# DVT-Buffer.net
KiCad netlist of a schematic drawn in Altium Designer
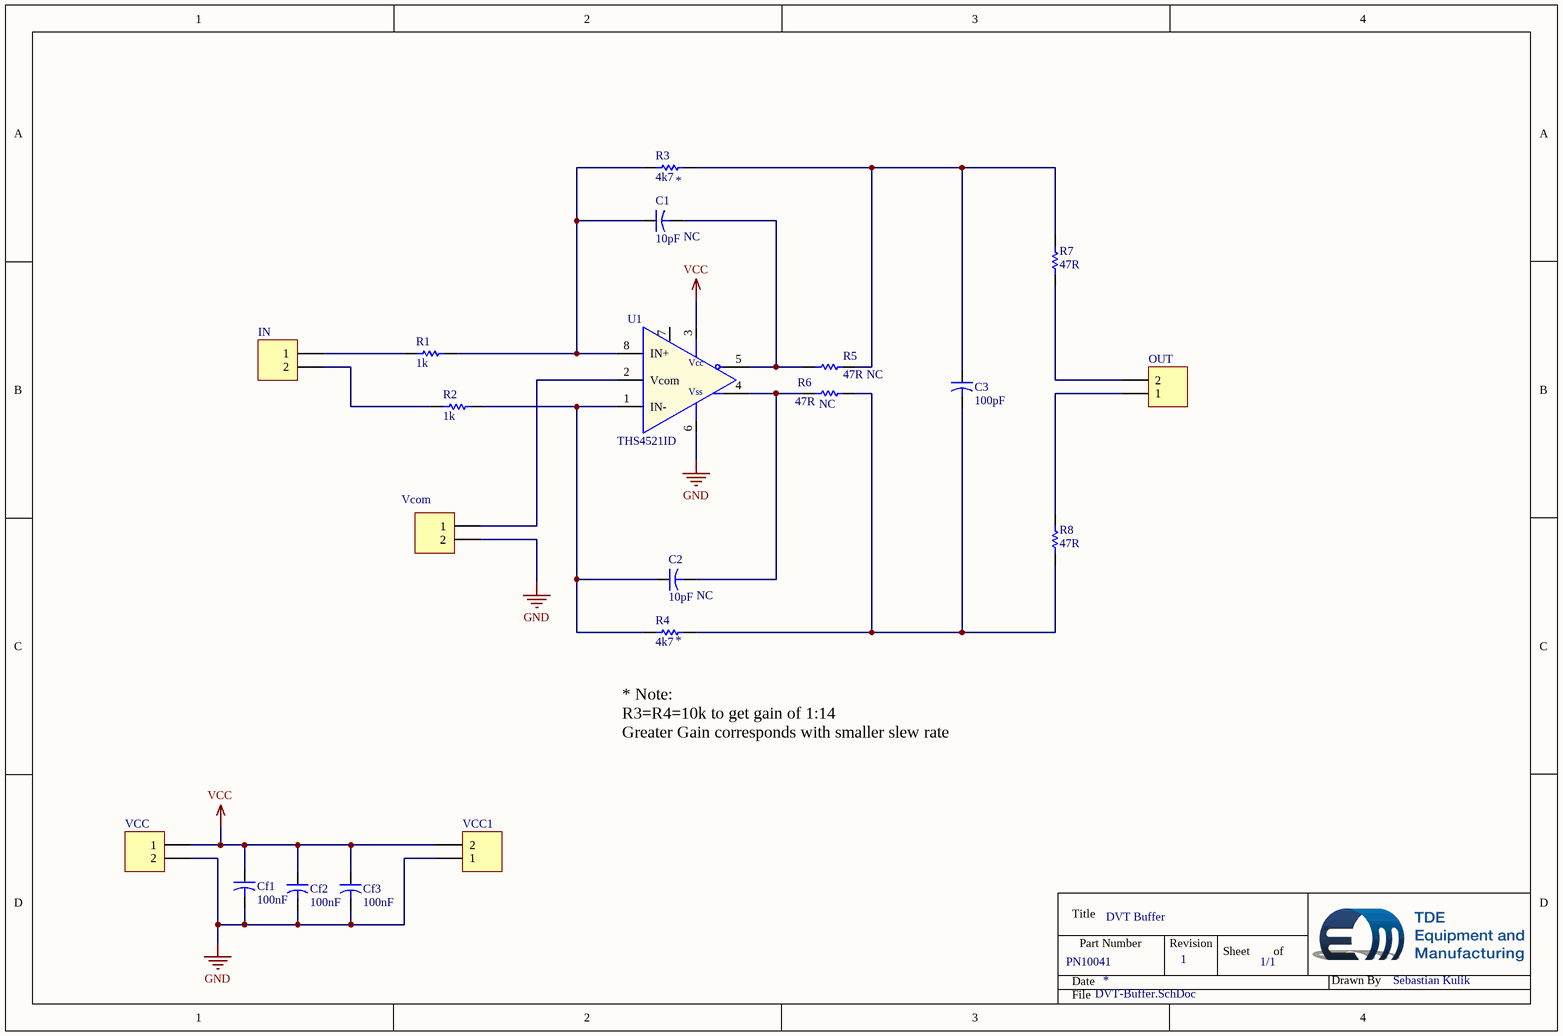
[diagram p0: DVT-Buffer.SchDoc]

(export (version "E")
  (design (tool "Eeschema 10.0.6"))
  (components
    (comp (ref "C1")
      (value "10pF")
      (footprint "Dummy-10mm")
      (description "Capacitor-Dummy-THT")
      (fields (field (name "PUBLISHER") "Sebastian Kulik"))
      (libsource (lib "Capacitors") (part "Capacitor-Dummy-THT"))
    )
    (comp (ref "C2")
      (value "10pF")
      (footprint "Dummy-10mm")
      (description "Capacitor-Dummy-THT")
      (fields (field (name "PUBLISHER") "Sebastian Kulik"))
      (libsource (lib "Capacitors") (part "Capacitor-Dummy-THT"))
    )
    (comp (ref "C3")
      (value "100pF")
      (footprint "Dummy-10mm")
      (description "Capacitor-Dummy-THT")
      (fields (field (name "PUBLISHER") "Sebastian Kulik"))
      (libsource (lib "Capacitors") (part "Capacitor-Dummy-THT"))
    )
    (comp (ref "Cf1")
      (value "100nF")
      (footprint "Dummy-10mm")
      (description "Capacitor-Dummy-THT")
      (fields (field (name "PUBLISHER") "Sebastian Kulik"))
      (libsource (lib "Capacitors") (part "Capacitor-Dummy-THT"))
    )
    (comp (ref "Cf2")
      (value "100nF")
      (footprint "Dummy-10mm")
      (description "Capacitor-Dummy-THT")
      (fields (field (name "PUBLISHER") "Sebastian Kulik"))
      (libsource (lib "Capacitors") (part "Capacitor-Dummy-THT"))
    )
    (comp (ref "Cf3")
      (value "100nF")
      (footprint "Dummy-10mm")
      (description "Capacitor-Dummy-THT")
      (fields (field (name "PUBLISHER") "Sebastian Kulik"))
      (libsource (lib "Capacitors") (part "Capacitor-Dummy-THT"))
    )
    (comp (ref "IN")
      (value "PHOENIX_1715721")
      (footprint "Phoenix-2-5_08")
      (description "Phoenix, 2 pol, 5.08mm, 22A, 715721")
      (fields (field (name "MANUFACTURER") "Phoenix") (field (name "PUBLISHER") "Sebastian Kulik"))
      (libsource (lib "") (part "2Pol_1715721_1"))
    )
    (comp (ref "OUT")
      (value "PHOENIX_1715721")
      (footprint "Phoenix-2-5_08")
      (description "Phoenix, 2 pol, 5.08mm, 22A, 715721")
      (fields (field (name "MANUFACTURER") "Phoenix") (field (name "PUBLISHER") "Sebastian Kulik"))
      (libsource (lib "Connectors") (part "2Pol_1715721"))
    )
    (comp (ref "R1")
      (value "1k")
      (footprint "Dummy-10mm")
      (description "Resistor-Dummy-THT")
      (fields (field (name "PUBLISHER") "Sebastian Kulik"))
      (libsource (lib "Resistors") (part "Resistor-Dummy-THT"))
    )
    (comp (ref "R2")
      (value "1k")
      (footprint "Dummy-10mm")
      (description "Resistor-Dummy-THT")
      (fields (field (name "PUBLISHER") "Sebastian Kulik"))
      (libsource (lib "Resistors") (part "Resistor-Dummy-THT"))
    )
    (comp (ref "R3")
      (value "4k7")
      (footprint "Dummy-10mm")
      (description "Resistor-Dummy-THT")
      (fields (field (name "PUBLISHER") "Sebastian Kulik"))
      (libsource (lib "Resistors") (part "Resistor-Dummy-THT"))
    )
    (comp (ref "R4")
      (value "4k7")
      (footprint "Dummy-10mm")
      (description "Resistor-Dummy-THT")
      (fields (field (name "PUBLISHER") "Sebastian Kulik"))
      (libsource (lib "Resistors") (part "Resistor-Dummy-THT"))
    )
    (comp (ref "R5")
      (value "47R")
      (footprint "Dummy-10mm")
      (description "Resistor-Dummy-THT")
      (fields (field (name "PUBLISHER") "Sebastian Kulik"))
      (libsource (lib "Resistors") (part "Resistor-Dummy-THT"))
    )
    (comp (ref "R6")
      (value "47R")
      (footprint "Dummy-10mm")
      (description "Resistor-Dummy-THT")
      (fields (field (name "PUBLISHER") "Sebastian Kulik"))
      (libsource (lib "Resistors") (part "Resistor-Dummy-THT"))
    )
    (comp (ref "R7")
      (value "47R")
      (footprint "Dummy-10mm")
      (description "Resistor-Dummy-THT")
      (fields (field (name "PUBLISHER") "Sebastian Kulik"))
      (libsource (lib "Resistors") (part "Resistor-Dummy-THT"))
    )
    (comp (ref "R8")
      (value "47R")
      (footprint "Dummy-10mm")
      (description "Resistor-Dummy-THT")
      (fields (field (name "PUBLISHER") "Sebastian Kulik"))
      (libsource (lib "Resistors") (part "Resistor-Dummy-THT"))
    )
    (comp (ref "U1")
      (value "THS4521ID")
      (footprint "TSSOP8")
      (description "Fully differential OP, 50MHz")
      (fields (field (name "MANUFACTURER") "TI") (field (name "PUBLISHER") "Sebastian Kulik"))
      (libsource (lib "ICs") (part "THS4521ID"))
    )
    (comp (ref "VCC")
      (value "PHOENIX_1715721")
      (footprint "Phoenix-2-5_08")
      (description "Phoenix, 2 pol, 5.08mm, 22A, 715721")
      (fields (field (name "MANUFACTURER") "Phoenix") (field (name "PUBLISHER") "Sebastian Kulik"))
      (libsource (lib "") (part "2Pol_1715721_1"))
    )
    (comp (ref "VCC1")
      (value "PHOENIX_1715721")
      (footprint "Phoenix-2-5_08")
      (description "Phoenix, 2 pol, 5.08mm, 22A, 715721")
      (fields (field (name "MANUFACTURER") "Phoenix") (field (name "PUBLISHER") "Sebastian Kulik"))
      (libsource (lib "Connectors") (part "2Pol_1715721"))
    )
    (comp (ref "Vcom")
      (value "Plug_2_90_2.54")
      (footprint "HDR1X2")
      (description "Plug, 2-Pin")
      (fields (field (name "MANUFACTURER") "WE") (field (name "PUBLISHER") "Sebastian Kulik"))
      (libsource (lib "Connectors") (part "Plug_2_90_2.54"))
    )
  )
  (nets
    (net (code "1") (name "GND") (class "Default")
      (node (ref "Cf1") (pin "2") (pinfunction "2_2") (pintype "passive"))
      (node (ref "Cf2") (pin "2") (pinfunction "2_2") (pintype "passive"))
      (node (ref "Cf3") (pin "2") (pinfunction "2_2") (pintype "passive"))
      (node (ref "U1") (pin "6") (pinfunction "Vss_6") (pintype "passive"))
      (node (ref "VCC") (pin "2") (pinfunction "2_2") (pintype "passive"))
      (node (ref "VCC1") (pin "1") (pinfunction "1_1") (pintype "passive"))
      (node (ref "Vcom") (pin "2") (pinfunction "2_2") (pintype "passive"))
    )
    (net (code "2") (name "Net-(C3-Pad1)") (class "Default")
      (node (ref "C3") (pin "1") (pinfunction "1_1") (pintype "passive"))
      (node (ref "R3") (pin "2") (pinfunction "2_2") (pintype "passive"))
      (node (ref "R5") (pin "2") (pinfunction "2_2") (pintype "passive"))
      (node (ref "R7") (pin "2") (pinfunction "2_2") (pintype "passive"))
    )
    (net (code "3") (name "Net-(C3-Pad2)") (class "Default")
      (node (ref "C3") (pin "2") (pinfunction "2_2") (pintype "passive"))
      (node (ref "R4") (pin "2") (pinfunction "2_2") (pintype "passive"))
      (node (ref "R6") (pin "2") (pinfunction "2_2") (pintype "passive"))
      (node (ref "R8") (pin "1") (pinfunction "1_1") (pintype "passive"))
    )
    (net (code "4") (name "Net-(IN-Pad1)") (class "Default")
      (node (ref "IN") (pin "1") (pinfunction "1_1") (pintype "passive"))
      (node (ref "R1") (pin "1") (pinfunction "1_1") (pintype "passive"))
    )
    (net (code "5") (name "Net-(IN-Pad2)") (class "Default")
      (node (ref "IN") (pin "2") (pinfunction "2_2") (pintype "passive"))
      (node (ref "R2") (pin "1") (pinfunction "1_1") (pintype "passive"))
    )
    (net (code "6") (name "Net-(OUT-Pad1)") (class "Default")
      (node (ref "OUT") (pin "1") (pinfunction "1_1") (pintype "passive"))
      (node (ref "R8") (pin "2") (pinfunction "2_2") (pintype "passive"))
    )
    (net (code "7") (name "Net-(OUT-Pad2)") (class "Default")
      (node (ref "OUT") (pin "2") (pinfunction "2_2") (pintype "passive"))
      (node (ref "R7") (pin "1") (pinfunction "1_1") (pintype "passive"))
    )
    (net (code "8") (name "Net-(U1-IN+)") (class "Default")
      (node (ref "C1") (pin "1") (pinfunction "1_1") (pintype "passive"))
      (node (ref "R1") (pin "2") (pinfunction "2_2") (pintype "passive"))
      (node (ref "R3") (pin "1") (pinfunction "1_1") (pintype "passive"))
      (node (ref "U1") (pin "8") (pinfunction "IN+_8") (pintype "power_in"))
    )
    (net (code "9") (name "Net-(U1-IN-)") (class "Default")
      (node (ref "C2") (pin "1") (pinfunction "1_1") (pintype "passive"))
      (node (ref "R2") (pin "2") (pinfunction "2_2") (pintype "passive"))
      (node (ref "R4") (pin "1") (pinfunction "1_1") (pintype "passive"))
      (node (ref "U1") (pin "1") (pinfunction "IN-_1") (pintype "passive"))
    )
    (net (code "10") (name "Net-(U1-OUT+)") (class "Default")
      (node (ref "C1") (pin "2") (pinfunction "2_2") (pintype "passive"))
      (node (ref "R5") (pin "1") (pinfunction "1_1") (pintype "passive"))
      (node (ref "U1") (pin "5") (pinfunction "OUT+_5") (pintype "power_in"))
    )
    (net (code "11") (name "Net-(U1-OUT-)") (class "Default")
      (node (ref "C2") (pin "2") (pinfunction "2_2") (pintype "passive"))
      (node (ref "R6") (pin "1") (pinfunction "1_1") (pintype "passive"))
      (node (ref "U1") (pin "4") (pinfunction "OUT-_4") (pintype "passive"))
    )
    (net (code "12") (name "Net-(U1-Vcom)") (class "Default")
      (node (ref "U1") (pin "2") (pinfunction "Vcom_2") (pintype "passive"))
      (node (ref "Vcom") (pin "1") (pinfunction "1_1") (pintype "passive"))
    )
    (net (code "13") (name "VCC") (class "Default")
      (node (ref "Cf1") (pin "1") (pinfunction "1_1") (pintype "passive"))
      (node (ref "Cf2") (pin "1") (pinfunction "1_1") (pintype "passive"))
      (node (ref "Cf3") (pin "1") (pinfunction "1_1") (pintype "passive"))
      (node (ref "U1") (pin "3") (pinfunction "Vcc_3") (pintype "passive"))
      (node (ref "VCC") (pin "1") (pinfunction "1_1") (pintype "passive"))
      (node (ref "VCC1") (pin "2") (pinfunction "2_2") (pintype "passive"))
    )
    (net (code "14") (name "unconnected-(U1-PD-Pad7)") (class "Default")
      (node (ref "U1") (pin "7") (pinfunction "PD_7") (pintype "passive"))
    )
  )
)
